# MCU.net
KiCad netlist of a schematic drawn in Altium Designer
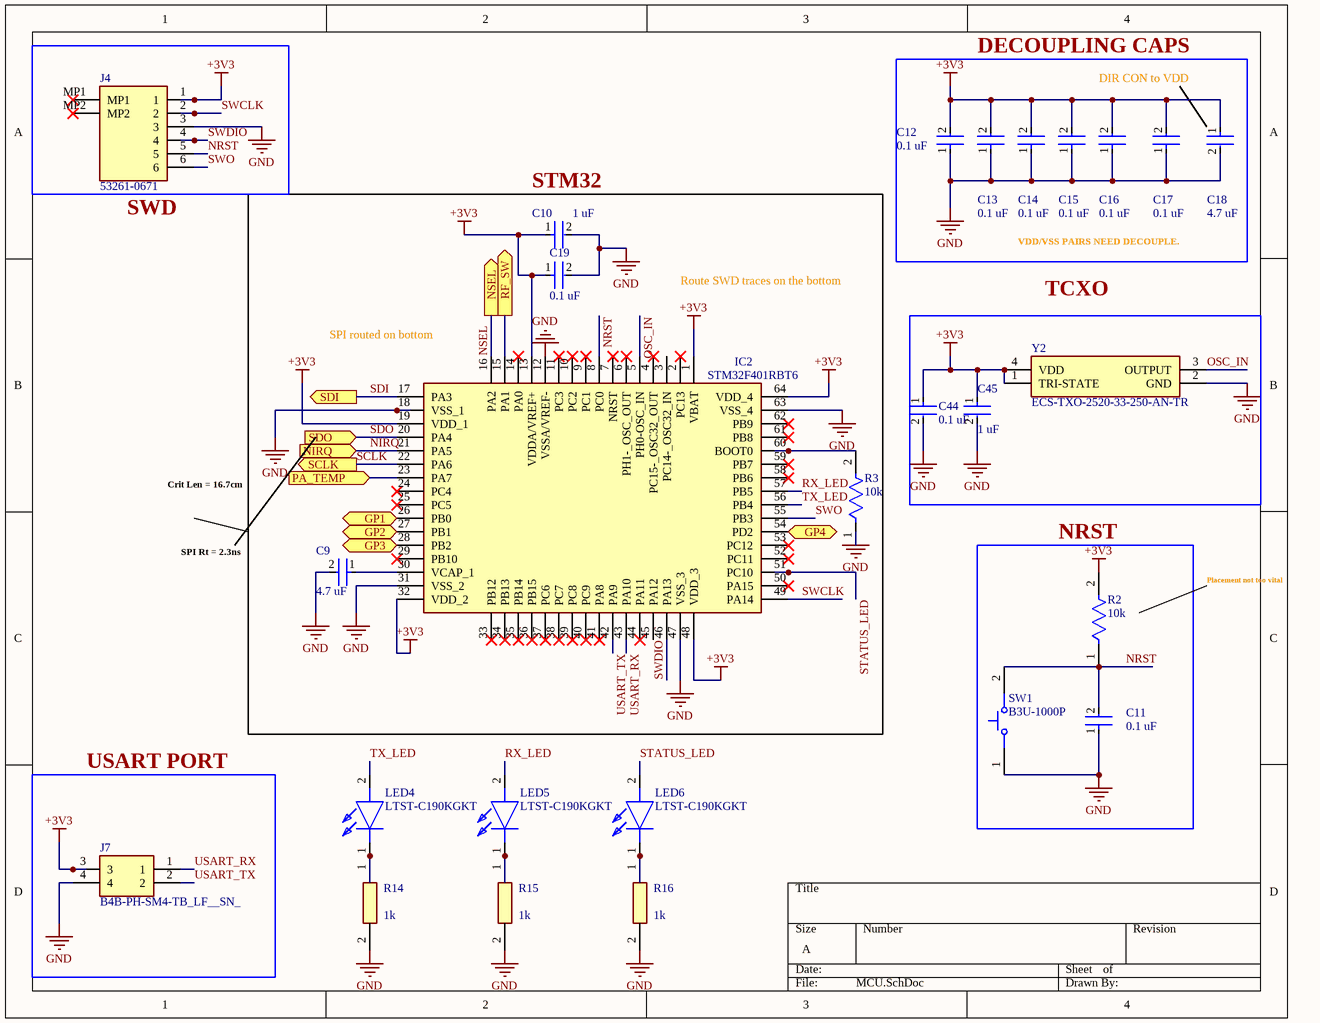
[diagram p0: MCU.SchDoc]

(export (version "E")
  (design (tool "Eeschema 10.0.6"))
  (components
    (comp (ref "C9")
      (value "4.7 uF")
      (footprint "FP-GRM188-0_15-IPC_C")
      (fields (field (name "VOLTAGE") "25V") (field (name "TOLERANCE") "10%"))
      (libsource (lib "Altium Content Vault") (part "02cd4be3c70576c341d710602a673aa"))
    )
    (comp (ref "C10")
      (value "1 uF")
      (footprint "FP-C0402C105K9PACTU-MFG")
      (description "CAP CER 1UF 6.3V X5R 0402 Name: C0402C105K9PACTU")
      (fields (field (name "TOLERANCE") "10%") (field (name "VOLTAGE") "6.3V"))
      (libsource (lib "Altium Content Vault") (part "11868f565c42a9108669ba33697ecf6"))
    )
    (comp (ref "C11")
      (value "0.1 uF")
      (footprint "FP-GRM033-0_03-MFG")
      (fields (field (name "TOLERANCE") "10%"))
      (libsource (lib "Altium Content Vault") (part "b4654b650e69147ec39a6b967a45e02"))
    )
    (comp (ref "C12")
      (value "0.1 uF")
      (footprint "FP-GRM033-0_03-MFG")
      (fields (field (name "TOLERANCE") "10%"))
      (libsource (lib "Altium Content Vault") (part "b4654b650e69147ec39a6b967a45e02"))
    )
    (comp (ref "C13")
      (value "0.1 uF")
      (footprint "FP-GRM033-0_03-MFG")
      (fields (field (name "TOLERANCE") "10%"))
      (libsource (lib "Altium Content Vault") (part "b4654b650e69147ec39a6b967a45e02"))
    )
    (comp (ref "C14")
      (value "0.1 uF")
      (footprint "FP-GRM033-0_03-MFG")
      (fields (field (name "TOLERANCE") "10%"))
      (libsource (lib "Altium Content Vault") (part "b4654b650e69147ec39a6b967a45e02"))
    )
    (comp (ref "C15")
      (value "0.1 uF")
      (footprint "FP-GRM033-0_03-MFG")
      (fields (field (name "TOLERANCE") "10%"))
      (libsource (lib "Altium Content Vault") (part "b4654b650e69147ec39a6b967a45e02"))
    )
    (comp (ref "C16")
      (value "0.1 uF")
      (footprint "FP-GRM033-0_03-MFG")
      (fields (field (name "TOLERANCE") "10%"))
      (libsource (lib "Altium Content Vault") (part "b4654b650e69147ec39a6b967a45e02"))
    )
    (comp (ref "C17")
      (value "0.1 uF")
      (footprint "FP-GRM033-0_03-MFG")
      (fields (field (name "TOLERANCE") "10%"))
      (libsource (lib "Altium Content Vault") (part "b4654b650e69147ec39a6b967a45e02"))
    )
    (comp (ref "C18")
      (value "4.7 uF")
      (footprint "FP-GRM188-0_15-IPC_C")
      (fields (field (name "VOLTAGE") "25V") (field (name "TOLERANCE") "10%"))
      (libsource (lib "Altium Content Vault") (part "02cd4be3c70576c341d710602a673aa"))
    )
    (comp (ref "C19")
      (value "0.1 uF")
      (footprint "FP-GRM033-0_03-MFG")
      (fields (field (name "TOLERANCE") "10%"))
      (libsource (lib "Altium Content Vault") (part "b4654b650e69147ec39a6b967a45e02"))
    )
    (comp (ref "C44")
      (value "0.1 uF")
      (footprint "FP-GRM033-0_03-MFG")
      (fields (field (name "TOLERANCE") "10%"))
      (libsource (lib "Altium Content Vault") (part "b4654b650e69147ec39a6b967a45e02"))
    )
    (comp (ref "C45")
      (value "1 uF")
      (footprint "FP-C0402C105K9PACTU-MFG")
      (description "CAP CER 1UF 6.3V X5R 0402 Name: C0402C105K9PACTU")
      (fields (field (name "TOLERANCE") "10%") (field (name "VOLTAGE") "6.3V"))
      (libsource (lib "Altium Content Vault") (part "11868f565c42a9108669ba33697ecf6"))
    )
    (comp (ref "IC2")
      (value "STM32F401RBT6")
      (footprint "SamacSys:QFP50P1200X1200X160-64N")
      (description "Integrated Circuit")
      (fields (field (name "MOUSER PART NUMBER") "511-STM32F401RBT6"))
      (libsource (lib "*") (part "STM32F401RBT6"))
    )
    (comp (ref "J4")
      (value "53261-0671")
      (footprint "SamacSys:532610671")
      (description "Connector")
      (fields (field (name "MOUSER PART NUMBER") "538-53261-0671"))
      (libsource (lib "*") (part "53261-0671"))
    )
    (comp (ref "J7")
      (value "B4B-PH-SM4-TB_LF__SN_")
      (footprint "SamacSys:B4B-PH-SM4_1")
      (description "Connector")
      (fields (field (name "MANUFACTURER_PART_NUMBER") "B4B-PH-SM4-TB(LF)(SN)"))
      (libsource (lib "*") (part "B4B-PH-SM4-TB_LF__SN_"))
    )
    (comp (ref "LED4")
      (value "LTST-C190KGKT")
      (footprint "SamacSys:LEDC1608X80N")
      (description "LED")
      (fields (field (name "MOUSER PART NUMBER") "859-LTST-C190KGKT"))
      (libsource (lib "*") (part "LTST-C190KGKT"))
    )
    (comp (ref "LED5")
      (value "LTST-C190KGKT")
      (footprint "SamacSys:LEDC1608X80N")
      (description "LED")
      (fields (field (name "MOUSER PART NUMBER") "859-LTST-C190KGKT"))
      (libsource (lib "*") (part "LTST-C190KGKT"))
    )
    (comp (ref "LED6")
      (value "LTST-C190KGKT")
      (footprint "SamacSys:LEDC1608X80N")
      (description "LED")
      (fields (field (name "MOUSER PART NUMBER") "859-LTST-C190KGKT"))
      (libsource (lib "*") (part "LTST-C190KGKT"))
    )
    (comp (ref "R2")
      (value "10k")
      (footprint "FP-RMCF0402-IPC_C")
      (description "10kΩ ±1% 0.063W 0402 Thick Film Chip Resistor AEC-Q200 compliant Name: RMCF0402FT10K0")
      (fields (field (name "TOLERANCE") "1%"))
      (libsource (lib "Altium Content Vault") (part "1029c3af85768c4190bb7ad29bc67b5"))
    )
    (comp (ref "R3")
      (value "10k")
      (footprint "FP-RMCF0402-IPC_C")
      (description "10kΩ ±1% 0.063W 0402 Thick Film Chip Resistor AEC-Q200 compliant Name: RMCF0402FT10K0")
      (fields (field (name "TOLERANCE") "1%"))
      (libsource (lib "Altium Content Vault") (part "1029c3af85768c4190bb7ad29bc67b5"))
    )
    (comp (ref "R14")
      (value "1k")
      (footprint "SamacSys:RESC1608X55N")
      (description "RC0603FR-131KL")
      (fields (field (name "MOUSER PART NUMBER") "603-RC0603FR-131KL"))
      (libsource (lib "*") (part "RC0603FR-131KL"))
    )
    (comp (ref "R15")
      (value "1k")
      (footprint "SamacSys:RESC1608X55N")
      (description "RC0603FR-131KL")
      (fields (field (name "MOUSER PART NUMBER") "603-RC0603FR-131KL"))
      (libsource (lib "*") (part "RC0603FR-131KL"))
    )
    (comp (ref "R16")
      (value "1k")
      (footprint "SamacSys:RESC1608X55N")
      (description "RC0603FR-131KL")
      (fields (field (name "MOUSER PART NUMBER") "603-RC0603FR-131KL"))
      (libsource (lib "*") (part "RC0603FR-131KL"))
    )
    (comp (ref "SW1")
      (value "B3U-1000P")
      (footprint "OMRON-B3U-1000_V")
      (description "Tactile Switch, SPST-NO, 0.05 A, 12 V, -25 to 70 degC, 2-Pin SMD, RoHS, Tape and Reel")
      (fields (field (name "MANUFACTURER") "Omron Electronic Components"))
      (libsource (lib "Americas- Calgary to Space- Calgary University") (part "SW-SPST-NO-2"))
    )
    (comp (ref "Y2")
      (value "ECS-TXO-2520-33-250-AN-TR")
      (footprint "SamacSys:ECSTXO252033250ANTR")
      (description "Crystal or Oscillator")
      (fields (field (name "MOUSER PART NUMBER") "520-T2520-33-250-ANT"))
      (libsource (lib "*") (part "ECS-TXO-2520-33-250-AN-TR"))
    )
  )
  (nets
    (net (code "1") (name "+3V3") (class "Default")
      (node (ref "C10") (pin "1") (pinfunction "1_1") (pintype "passive"))
      (node (ref "C12") (pin "2") (pinfunction "2_2") (pintype "passive"))
      (node (ref "C13") (pin "2") (pinfunction "2_2") (pintype "passive"))
      (node (ref "C14") (pin "2") (pinfunction "2_2") (pintype "passive"))
      (node (ref "C15") (pin "2") (pinfunction "2_2") (pintype "passive"))
      (node (ref "C16") (pin "2") (pinfunction "2_2") (pintype "passive"))
      (node (ref "C17") (pin "2") (pinfunction "2_2") (pintype "passive"))
      (node (ref "C18") (pin "1") (pinfunction "1_1") (pintype "passive"))
      (node (ref "C19") (pin "1") (pinfunction "1_1") (pintype "passive"))
      (node (ref "C44") (pin "1") (pinfunction "1_1") (pintype "passive"))
      (node (ref "C45") (pin "1") (pinfunction "1_1") (pintype "passive"))
      (node (ref "IC2") (pin "1") (pinfunction "VBAT_1") (pintype "passive"))
      (node (ref "IC2") (pin "13") (pinfunction "VDDA/VREF+_13") (pintype "passive"))
      (node (ref "IC2") (pin "19") (pinfunction "VDD_1_19") (pintype "passive"))
      (node (ref "IC2") (pin "32") (pinfunction "VDD_2_32") (pintype "passive"))
      (node (ref "IC2") (pin "48") (pinfunction "VDD_3_48") (pintype "passive"))
      (node (ref "IC2") (pin "64") (pinfunction "VDD_4_64") (pintype "passive"))
      (node (ref "J4") (pin "1") (pinfunction "1_1") (pintype "passive"))
      (node (ref "J7") (pin "3") (pinfunction "3_3") (pintype "passive"))
      (node (ref "R2") (pin "2") (pinfunction "2_2") (pintype "passive"))
      (node (ref "Y2") (pin "1") (pinfunction "TRI-STATE_1") (pintype "passive"))
      (node (ref "Y2") (pin "4") (pinfunction "VDD_4") (pintype "passive"))
    )
    (net (code "2") (name "/GP1") (class "Default")
      (node (ref "IC2") (pin "26") (pinfunction "PB0_26") (pintype "passive"))
    )
    (net (code "3") (name "/GP2") (class "Default")
      (node (ref "IC2") (pin "27") (pinfunction "PB1_27") (pintype "passive"))
    )
    (net (code "4") (name "/GP3") (class "Default")
      (node (ref "IC2") (pin "28") (pinfunction "PB2_28") (pintype "passive"))
    )
    (net (code "5") (name "/GP4") (class "Default")
      (node (ref "IC2") (pin "54") (pinfunction "PD2_54") (pintype "passive"))
    )
    (net (code "6") (name "/NIRQ") (class "Default")
      (node (ref "IC2") (pin "21") (pinfunction "PA5_21") (pintype "passive"))
    )
    (net (code "7") (name "/NRST") (class "Default")
      (node (ref "C11") (pin "2") (pinfunction "2_2") (pintype "passive"))
      (node (ref "IC2") (pin "8") (pinfunction "PC0_8") (pintype "passive"))
      (node (ref "J4") (pin "5") (pinfunction "5_5") (pintype "passive"))
      (node (ref "R2") (pin "1") (pinfunction "1_1") (pintype "passive"))
      (node (ref "SW1") (pin "2") (pinfunction "2_2") (pintype "passive"))
    )
    (net (code "8") (name "/NSEL") (class "Default")
      (node (ref "IC2") (pin "16") (pinfunction "PA2_16") (pintype "passive"))
    )
    (net (code "9") (name "/OSC_IN") (class "Default")
      (node (ref "IC2") (pin "5") (pinfunction "PH0-OSC_IN_5") (pintype "passive"))
      (node (ref "Y2") (pin "3") (pinfunction "OUTPUT_3") (pintype "passive"))
    )
    (net (code "10") (name "/PA_TEMP") (class "Default")
      (node (ref "IC2") (pin "23") (pinfunction "PA7_23") (pintype "passive"))
    )
    (net (code "11") (name "/RF_SW") (class "Default")
      (node (ref "IC2") (pin "15") (pinfunction "PA1_15") (pintype "passive"))
    )
    (net (code "12") (name "/RX_LED") (class "Default")
      (node (ref "IC2") (pin "57") (pinfunction "PB5_57") (pintype "passive"))
      (node (ref "LED5") (pin "2") (pinfunction "A_2") (pintype "passive"))
    )
    (net (code "13") (name "/SCLK") (class "Default")
      (node (ref "IC2") (pin "22") (pinfunction "PA6_22") (pintype "passive"))
    )
    (net (code "14") (name "/SDI") (class "Default")
      (node (ref "IC2") (pin "17") (pinfunction "PA3_17") (pintype "passive"))
    )
    (net (code "15") (name "/SDO") (class "Default")
      (node (ref "IC2") (pin "20") (pinfunction "PA4_20") (pintype "passive"))
    )
    (net (code "16") (name "/STATUS_LED") (class "Default")
      (node (ref "IC2") (pin "51") (pinfunction "PC10_51") (pintype "passive"))
      (node (ref "LED6") (pin "2") (pinfunction "A_2") (pintype "passive"))
    )
    (net (code "17") (name "/SWCLK") (class "Default")
      (node (ref "IC2") (pin "49") (pinfunction "PA14_49") (pintype "passive"))
      (node (ref "J4") (pin "2") (pinfunction "2_2") (pintype "passive"))
    )
    (net (code "18") (name "/SWDIO") (class "Default")
      (node (ref "IC2") (pin "46") (pinfunction "PA13_46") (pintype "passive"))
      (node (ref "J4") (pin "4") (pinfunction "4_4") (pintype "passive"))
    )
    (net (code "19") (name "/SWO") (class "Default")
      (node (ref "IC2") (pin "55") (pinfunction "PB3_55") (pintype "passive"))
      (node (ref "J4") (pin "6") (pinfunction "6_6") (pintype "passive"))
    )
    (net (code "20") (name "/TX_LED") (class "Default")
      (node (ref "IC2") (pin "56") (pinfunction "PB4_56") (pintype "passive"))
      (node (ref "LED4") (pin "2") (pinfunction "A_2") (pintype "passive"))
    )
    (net (code "21") (name "/USART_RX") (class "Default")
      (node (ref "IC2") (pin "43") (pinfunction "PA10_43") (pintype "passive"))
      (node (ref "J7") (pin "1") (pinfunction "1_1") (pintype "passive"))
    )
    (net (code "22") (name "/USART_TX") (class "Default")
      (node (ref "IC2") (pin "42") (pinfunction "PA9_42") (pintype "passive"))
      (node (ref "J7") (pin "2") (pinfunction "2_2") (pintype "passive"))
    )
    (net (code "23") (name "GND") (class "Default")
      (node (ref "C10") (pin "2") (pinfunction "2_2") (pintype "passive"))
      (node (ref "C11") (pin "1") (pinfunction "1_1") (pintype "passive"))
      (node (ref "C12") (pin "1") (pinfunction "1_1") (pintype "passive"))
      (node (ref "C13") (pin "1") (pinfunction "1_1") (pintype "passive"))
      (node (ref "C14") (pin "1") (pinfunction "1_1") (pintype "passive"))
      (node (ref "C15") (pin "1") (pinfunction "1_1") (pintype "passive"))
      (node (ref "C16") (pin "1") (pinfunction "1_1") (pintype "passive"))
      (node (ref "C17") (pin "1") (pinfunction "1_1") (pintype "passive"))
      (node (ref "C18") (pin "2") (pinfunction "2_2") (pintype "passive"))
      (node (ref "C19") (pin "2") (pinfunction "2_2") (pintype "passive"))
      (node (ref "C44") (pin "2") (pinfunction "2_2") (pintype "passive"))
      (node (ref "C45") (pin "2") (pinfunction "2_2") (pintype "passive"))
      (node (ref "C9") (pin "2") (pinfunction "2_2") (pintype "passive"))
      (node (ref "IC2") (pin "12") (pinfunction "VSSA/VREF-_12") (pintype "passive"))
      (node (ref "IC2") (pin "18") (pinfunction "VSS_1_18") (pintype "passive"))
      (node (ref "IC2") (pin "31") (pinfunction "VSS_2_31") (pintype "passive"))
      (node (ref "IC2") (pin "47") (pinfunction "VSS_3_47") (pintype "passive"))
      (node (ref "IC2") (pin "63") (pinfunction "VSS_4_63") (pintype "passive"))
      (node (ref "J4") (pin "3") (pinfunction "3_3") (pintype "passive"))
      (node (ref "J7") (pin "4") (pinfunction "4_4") (pintype "passive"))
      (node (ref "R14") (pin "2") (pinfunction "2_2") (pintype "passive"))
      (node (ref "R15") (pin "2") (pinfunction "2_2") (pintype "passive"))
      (node (ref "R16") (pin "2") (pinfunction "2_2") (pintype "passive"))
      (node (ref "R3") (pin "1") (pinfunction "1_1") (pintype "passive"))
      (node (ref "SW1") (pin "1") (pinfunction "1_1") (pintype "passive"))
      (node (ref "Y2") (pin "2") (pinfunction "GND_2") (pintype "passive"))
    )
    (net (code "24") (name "Net-(IC2-BOOT0)") (class "Default")
      (node (ref "IC2") (pin "60") (pinfunction "BOOT0_60") (pintype "passive"))
      (node (ref "R3") (pin "2") (pinfunction "2_2") (pintype "passive"))
    )
    (net (code "25") (name "Net-(IC2-VCAP_1)") (class "Default")
      (node (ref "C9") (pin "1") (pinfunction "1_1") (pintype "passive"))
      (node (ref "IC2") (pin "30") (pinfunction "VCAP_1_30") (pintype "passive"))
    )
    (net (code "26") (name "Net-(LED4-K)") (class "Default")
      (node (ref "LED4") (pin "1") (pinfunction "K_1") (pintype "passive"))
      (node (ref "R14") (pin "1") (pinfunction "1_1") (pintype "passive"))
    )
    (net (code "27") (name "Net-(LED5-K)") (class "Default")
      (node (ref "LED5") (pin "1") (pinfunction "K_1") (pintype "passive"))
      (node (ref "R15") (pin "1") (pinfunction "1_1") (pintype "passive"))
    )
    (net (code "28") (name "Net-(LED6-K)") (class "Default")
      (node (ref "LED6") (pin "1") (pinfunction "K_1") (pintype "passive"))
      (node (ref "R16") (pin "1") (pinfunction "1_1") (pintype "passive"))
    )
    (net (code "29") (name "unconnected-(IC2-NRST-Pad7)") (class "Default")
      (node (ref "IC2") (pin "7") (pinfunction "NRST_7") (pintype "passive+no_connect"))
    )
    (net (code "30") (name "unconnected-(IC2-PA0-Pad14)") (class "Default")
      (node (ref "IC2") (pin "14") (pinfunction "PA0_14") (pintype "passive+no_connect"))
    )
    (net (code "31") (name "unconnected-(IC2-PA8-Pad41)") (class "Default")
      (node (ref "IC2") (pin "41") (pinfunction "PA8_41") (pintype "passive+no_connect"))
    )
    (net (code "32") (name "unconnected-(IC2-PA11-Pad44)") (class "Default")
      (node (ref "IC2") (pin "44") (pinfunction "PA11_44") (pintype "passive+no_connect"))
    )
    (net (code "33") (name "unconnected-(IC2-PA12-Pad45)") (class "Default")
      (node (ref "IC2") (pin "45") (pinfunction "PA12_45") (pintype "passive"))
    )
    (net (code "34") (name "unconnected-(IC2-PA15-Pad50)") (class "Default")
      (node (ref "IC2") (pin "50") (pinfunction "PA15_50") (pintype "passive+no_connect"))
    )
    (net (code "35") (name "unconnected-(IC2-PB6-Pad58)") (class "Default")
      (node (ref "IC2") (pin "58") (pinfunction "PB6_58") (pintype "passive+no_connect"))
    )
    (net (code "36") (name "unconnected-(IC2-PB7-Pad59)") (class "Default")
      (node (ref "IC2") (pin "59") (pinfunction "PB7_59") (pintype "passive+no_connect"))
    )
    (net (code "37") (name "unconnected-(IC2-PB8-Pad61)") (class "Default")
      (node (ref "IC2") (pin "61") (pinfunction "PB8_61") (pintype "passive+no_connect"))
    )
    (net (code "38") (name "unconnected-(IC2-PB9-Pad62)") (class "Default")
      (node (ref "IC2") (pin "62") (pinfunction "PB9_62") (pintype "passive+no_connect"))
    )
    (net (code "39") (name "unconnected-(IC2-PB10-Pad29)") (class "Default")
      (node (ref "IC2") (pin "29") (pinfunction "PB10_29") (pintype "passive+no_connect"))
    )
    (net (code "40") (name "unconnected-(IC2-PB12-Pad33)") (class "Default")
      (node (ref "IC2") (pin "33") (pinfunction "PB12_33") (pintype "passive+no_connect"))
    )
    (net (code "41") (name "unconnected-(IC2-PB13-Pad34)") (class "Default")
      (node (ref "IC2") (pin "34") (pinfunction "PB13_34") (pintype "passive+no_connect"))
    )
    (net (code "42") (name "unconnected-(IC2-PB14-Pad35)") (class "Default")
      (node (ref "IC2") (pin "35") (pinfunction "PB14_35") (pintype "passive+no_connect"))
    )
    (net (code "43") (name "unconnected-(IC2-PB15-Pad36)") (class "Default")
      (node (ref "IC2") (pin "36") (pinfunction "PB15_36") (pintype "passive+no_connect"))
    )
    (net (code "44") (name "unconnected-(IC2-PC1-Pad9)") (class "Default")
      (node (ref "IC2") (pin "9") (pinfunction "PC1_9") (pintype "passive+no_connect"))
    )
    (net (code "45") (name "unconnected-(IC2-PC2-Pad10)") (class "Default")
      (node (ref "IC2") (pin "10") (pinfunction "PC2_10") (pintype "passive+no_connect"))
    )
    (net (code "46") (name "unconnected-(IC2-PC3-Pad11)") (class "Default")
      (node (ref "IC2") (pin "11") (pinfunction "PC3_11") (pintype "passive+no_connect"))
    )
    (net (code "47") (name "unconnected-(IC2-PC4-Pad24)") (class "Default")
      (node (ref "IC2") (pin "24") (pinfunction "PC4_24") (pintype "passive+no_connect"))
    )
    (net (code "48") (name "unconnected-(IC2-PC5-Pad25)") (class "Default")
      (node (ref "IC2") (pin "25") (pinfunction "PC5_25") (pintype "passive+no_connect"))
    )
    (net (code "49") (name "unconnected-(IC2-PC6-Pad37)") (class "Default")
      (node (ref "IC2") (pin "37") (pinfunction "PC6_37") (pintype "passive+no_connect"))
    )
    (net (code "50") (name "unconnected-(IC2-PC7-Pad38)") (class "Default")
      (node (ref "IC2") (pin "38") (pinfunction "PC7_38") (pintype "passive+no_connect"))
    )
    (net (code "51") (name "unconnected-(IC2-PC8-Pad39)") (class "Default")
      (node (ref "IC2") (pin "39") (pinfunction "PC8_39") (pintype "passive+no_connect"))
    )
    (net (code "52") (name "unconnected-(IC2-PC9-Pad40)") (class "Default")
      (node (ref "IC2") (pin "40") (pinfunction "PC9_40") (pintype "passive+no_connect"))
    )
    (net (code "53") (name "unconnected-(IC2-PC11-Pad52)") (class "Default")
      (node (ref "IC2") (pin "52") (pinfunction "PC11_52") (pintype "passive+no_connect"))
    )
    (net (code "54") (name "unconnected-(IC2-PC12-Pad53)") (class "Default")
      (node (ref "IC2") (pin "53") (pinfunction "PC12_53") (pintype "passive+no_connect"))
    )
    (net (code "55") (name "unconnected-(IC2-PC13-Pad2)") (class "Default")
      (node (ref "IC2") (pin "2") (pinfunction "PC13_2") (pintype "passive+no_connect"))
    )
    (net (code "56") (name "unconnected-(IC2-PC14-_OSC32_IN-Pad3)") (class "Default")
      (node (ref "IC2") (pin "3") (pinfunction "PC14-_OSC32_IN_3") (pintype "passive"))
    )
    (net (code "57") (name "unconnected-(IC2-PC15-_OSC32_OUT-Pad4)") (class "Default")
      (node (ref "IC2") (pin "4") (pinfunction "PC15-_OSC32_OUT_4") (pintype "passive+no_connect"))
    )
    (net (code "58") (name "unconnected-(IC2-PH1-_OSC_OUT-Pad6)") (class "Default")
      (node (ref "IC2") (pin "6") (pinfunction "PH1-_OSC_OUT_6") (pintype "passive+no_connect"))
    )
    (net (code "59") (name "unconnected-(J4-PadMP1)") (class "Default")
      (node (ref "J4") (pin "MP1") (pinfunction "MP1_MP1") (pintype "passive+no_connect"))
    )
    (net (code "60") (name "unconnected-(J4-PadMP2)") (class "Default")
      (node (ref "J4") (pin "MP2") (pinfunction "MP2_MP2") (pintype "passive+no_connect"))
    )
  )
)
